# Amplifier_AB_V1.net
KiCad netlist of a schematic drawn in EAGLE
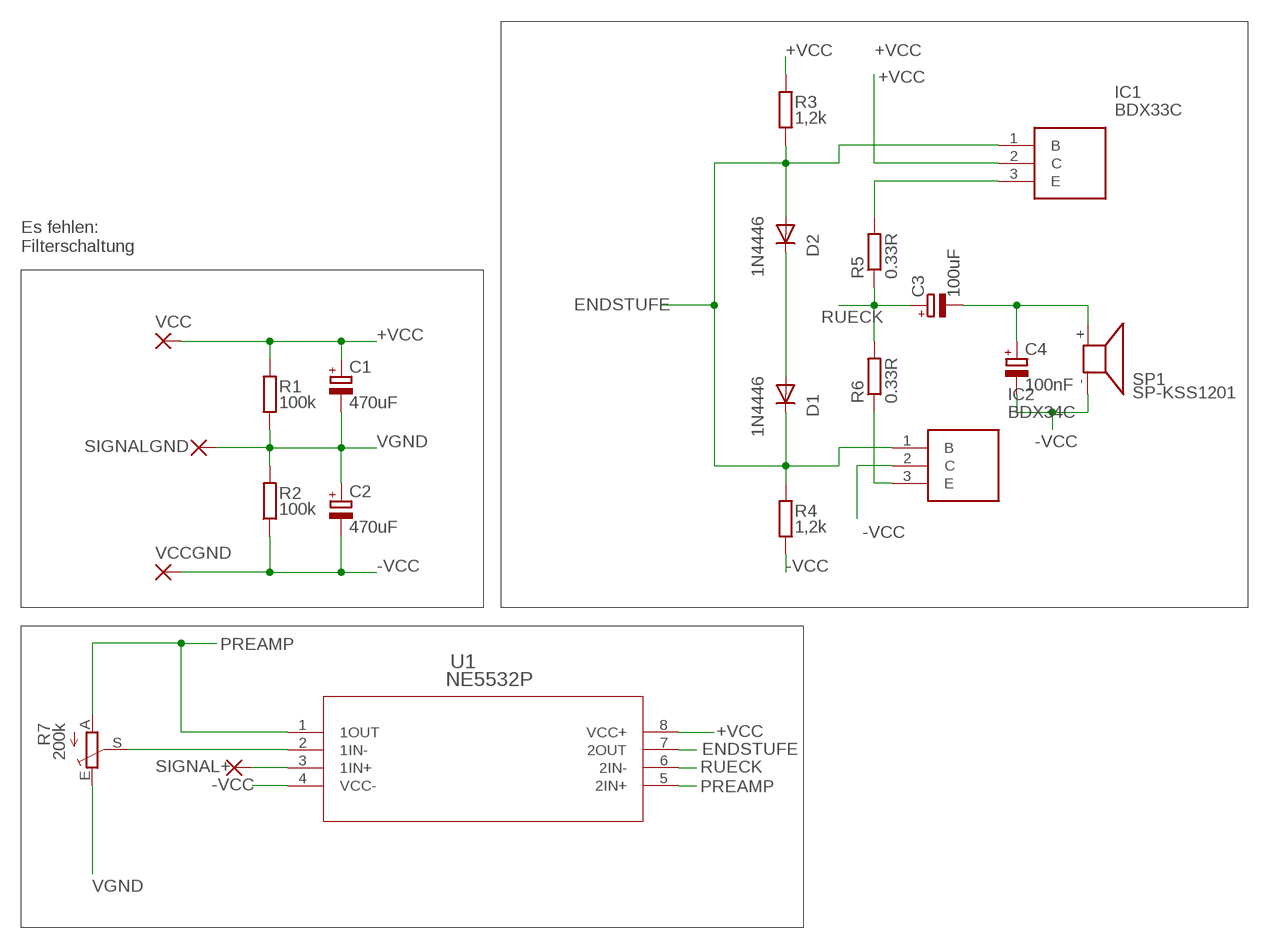
[diagram p0: schematic, sheet 1]

(export (version "E")
  (design (tool "Eeschema 10.0.6"))
  (components
    (comp (ref "C1")
      (value "470uF")
      (footprint "eagle-import:2,5-5")
      (libsource (lib "eagle-import") (part "CE_2,5-5"))
    )
    (comp (ref "C2")
      (value "470uF")
      (footprint "eagle-import:2,5-5")
      (libsource (lib "eagle-import") (part "CE_2,5-5"))
    )
    (comp (ref "C3")
      (value "100uF")
      (footprint "eagle-import:5-10,5")
      (libsource (lib "eagle-import") (part "CE_5-10,5"))
    )
    (comp (ref "C4")
      (value "100nF")
      (footprint "eagle-import:5-10,5")
      (libsource (lib "eagle-import") (part "CE_5-10,5"))
    )
    (comp (ref "D1")
      (value "1N4446")
      (footprint "eagle-import:DO35-10")
      (libsource (lib "eagle-import") (part "1N4446"))
    )
    (comp (ref "D2")
      (value "1N4446")
      (footprint "eagle-import:DO35-10")
      (libsource (lib "eagle-import") (part "1N4446"))
    )
    (comp (ref "IC1")
      (value "BDX33C")
      (footprint "eagle-import:TO270P460X1020X2008-3P")
      (fields (field (name "MOUSER_PART_NUMBER") "511-BDX33C"))
      (libsource (lib "eagle-import") (part "BDX33C"))
    )
    (comp (ref "IC2")
      (value "BDX34C")
      (footprint "eagle-import:TO270P460X1020X2008-3P")
      (fields (field (name "MOUSER_PART_NUMBER") "511-BDX34C"))
      (libsource (lib "eagle-import") (part "BDX34C"))
    )
    (comp (ref "R1")
      (value "100k")
      (footprint "eagle-import:0207_10")
      (libsource (lib "eagle-import") (part "R10"))
    )
    (comp (ref "R2")
      (value "100k")
      (footprint "eagle-import:0207_10")
      (libsource (lib "eagle-import") (part "R10"))
    )
    (comp (ref "R3")
      (value "1,2k")
      (footprint "eagle-import:0207_10")
      (libsource (lib "eagle-import") (part "R10"))
    )
    (comp (ref "R4")
      (value "1,2k")
      (footprint "eagle-import:0207_10")
      (libsource (lib "eagle-import") (part "R10"))
    )
    (comp (ref "R5")
      (value "0.33R")
      (footprint "eagle-import:0309_12")
      (libsource (lib "eagle-import") (part "R-EU_0309/12"))
    )
    (comp (ref "R6")
      (value "0.33R")
      (footprint "eagle-import:0309_12")
      (libsource (lib "eagle-import") (part "R-EU_0309/12"))
    )
    (comp (ref "R7")
      (value "200k")
      (footprint "eagle-import:CT6")
      (libsource (lib "eagle-import") (part "TRIM_EU-CT6"))
    )
    (comp (ref "SIGNAL+")
      (value "2,15/1,0")
      (footprint "eagle-import:2,15_1,0")
      (libsource (lib "eagle-import") (part "2,15/1,0"))
    )
    (comp (ref "SIGNALGND")
      (value "2,15/1,0")
      (footprint "eagle-import:2,15_1,0")
      (libsource (lib "eagle-import") (part "2,15/1,0"))
    )
    (comp (ref "SP1")
      (value "SP-KSS1201")
      (footprint "eagle-import:SP-KSS1201")
      (libsource (lib "eagle-import") (part "SP-KSS1201"))
    )
    (comp (ref "U1")
      (value "NE5532P")
      (footprint "eagle-import:P8")
      (fields (field (name "COPYRIGHT") "Copyright (C) 2023 Ultra Librarian. All rights reserved."))
      (libsource (lib "eagle-import") (part "NE5532P"))
    )
    (comp (ref "VCC")
      (value "2,15/1,0")
      (footprint "eagle-import:2,15_1,0")
      (libsource (lib "eagle-import") (part "2,15/1,0"))
    )
    (comp (ref "VCCGND")
      (value "2,15/1,0")
      (footprint "eagle-import:2,15_1,0")
      (libsource (lib "eagle-import") (part "2,15/1,0"))
    )
  )
  (nets
    (net (code "1") (name "/+VCC") (class "Default")
      (node (ref "C1") (pin "+") (pinfunction "+_+") (pintype "passive"))
      (node (ref "IC1") (pin "2") (pinfunction "C_2") (pintype "bidirectional"))
      (node (ref "R1") (pin "2") (pinfunction "2_2") (pintype "passive"))
      (node (ref "R3") (pin "2") (pinfunction "2_2") (pintype "passive"))
      (node (ref "U1") (pin "8") (pinfunction "VCC+_8") (pintype "power_in"))
      (node (ref "VCC") (pin "1") (pinfunction "P_1") (pintype "passive"))
    )
    (net (code "2") (name "/-VCC") (class "Default")
      (node (ref "C2") (pin "-") (pinfunction "-_-") (pintype "passive"))
      (node (ref "C4") (pin "-") (pinfunction "-_-") (pintype "passive"))
      (node (ref "IC2") (pin "2") (pinfunction "C_2") (pintype "bidirectional"))
      (node (ref "R2") (pin "1") (pinfunction "1_1") (pintype "passive"))
      (node (ref "R4") (pin "1") (pinfunction "1_1") (pintype "passive"))
      (node (ref "SP1") (pin "-") (pinfunction "2_-") (pintype "passive"))
      (node (ref "U1") (pin "4") (pinfunction "VCC-_4") (pintype "power_in"))
      (node (ref "VCCGND") (pin "1") (pinfunction "P_1") (pintype "passive"))
    )
    (net (code "3") (name "/ENDSTUFE") (class "Default")
      (node (ref "D1") (pin "C") (pinfunction "C_C") (pintype "passive"))
      (node (ref "D2") (pin "A") (pinfunction "A_A") (pintype "passive"))
      (node (ref "IC1") (pin "1") (pinfunction "B_1") (pintype "bidirectional"))
      (node (ref "IC2") (pin "1") (pinfunction "B_1") (pintype "bidirectional"))
      (node (ref "R3") (pin "1") (pinfunction "1_1") (pintype "passive"))
      (node (ref "R4") (pin "2") (pinfunction "2_2") (pintype "passive"))
      (node (ref "U1") (pin "7") (pinfunction "2OUT_7") (pintype "output"))
    )
    (net (code "4") (name "/PREAMP") (class "Default")
      (node (ref "R7") (pin "A") (pinfunction "A_A") (pintype "passive"))
      (node (ref "U1") (pin "1") (pinfunction "1OUT_1") (pintype "output"))
      (node (ref "U1") (pin "5") (pinfunction "2IN+_5") (pintype "input"))
    )
    (net (code "5") (name "/RUECK") (class "Default")
      (node (ref "C3") (pin "+") (pinfunction "+_+") (pintype "passive"))
      (node (ref "R5") (pin "1") (pinfunction "1_1") (pintype "passive"))
      (node (ref "R6") (pin "2") (pinfunction "2_2") (pintype "passive"))
      (node (ref "U1") (pin "6") (pinfunction "2IN-_6") (pintype "input"))
    )
    (net (code "6") (name "/VGND") (class "Default")
      (node (ref "C1") (pin "-") (pinfunction "-_-") (pintype "passive"))
      (node (ref "C2") (pin "+") (pinfunction "+_+") (pintype "passive"))
      (node (ref "R1") (pin "1") (pinfunction "1_1") (pintype "passive"))
      (node (ref "R2") (pin "2") (pinfunction "2_2") (pintype "passive"))
      (node (ref "R7") (pin "E") (pinfunction "E_E") (pintype "passive"))
      (node (ref "SIGNALGND") (pin "1") (pinfunction "P_1") (pintype "passive"))
    )
    (net (code "7") (name "Net-(D1-PadA)") (class "Default")
      (node (ref "D1") (pin "A") (pinfunction "A_A") (pintype "passive"))
      (node (ref "D2") (pin "C") (pinfunction "C_C") (pintype "passive"))
    )
    (net (code "8") (name "Net-(IC1-E)") (class "Default")
      (node (ref "IC1") (pin "3") (pinfunction "E_3") (pintype "bidirectional"))
      (node (ref "R5") (pin "2") (pinfunction "2_2") (pintype "passive"))
    )
    (net (code "9") (name "Net-(IC2-E)") (class "Default")
      (node (ref "IC2") (pin "3") (pinfunction "E_3") (pintype "bidirectional"))
      (node (ref "R6") (pin "1") (pinfunction "1_1") (pintype "passive"))
    )
    (net (code "10") (name "Net-(SIGNAL+-P)") (class "Default")
      (node (ref "SIGNAL+") (pin "1") (pinfunction "P_1") (pintype "passive"))
      (node (ref "U1") (pin "3") (pinfunction "1IN+_3") (pintype "input"))
    )
    (net (code "11") (name "Net-(SP1-1)") (class "Default")
      (node (ref "C3") (pin "-") (pinfunction "-_-") (pintype "passive"))
      (node (ref "C4") (pin "+") (pinfunction "+_+") (pintype "passive"))
      (node (ref "SP1") (pin "+") (pinfunction "1_+") (pintype "passive"))
    )
    (net (code "12") (name "Net-(U1-1IN-)") (class "Default")
      (node (ref "R7") (pin "S") (pinfunction "S_S") (pintype "passive"))
      (node (ref "U1") (pin "2") (pinfunction "1IN-_2") (pintype "input"))
    )
  )
)
